# Macro_Keyboard_32u4_Row_Column_MiniMacro.net
KiCad netlist of a schematic drawn in EAGLE
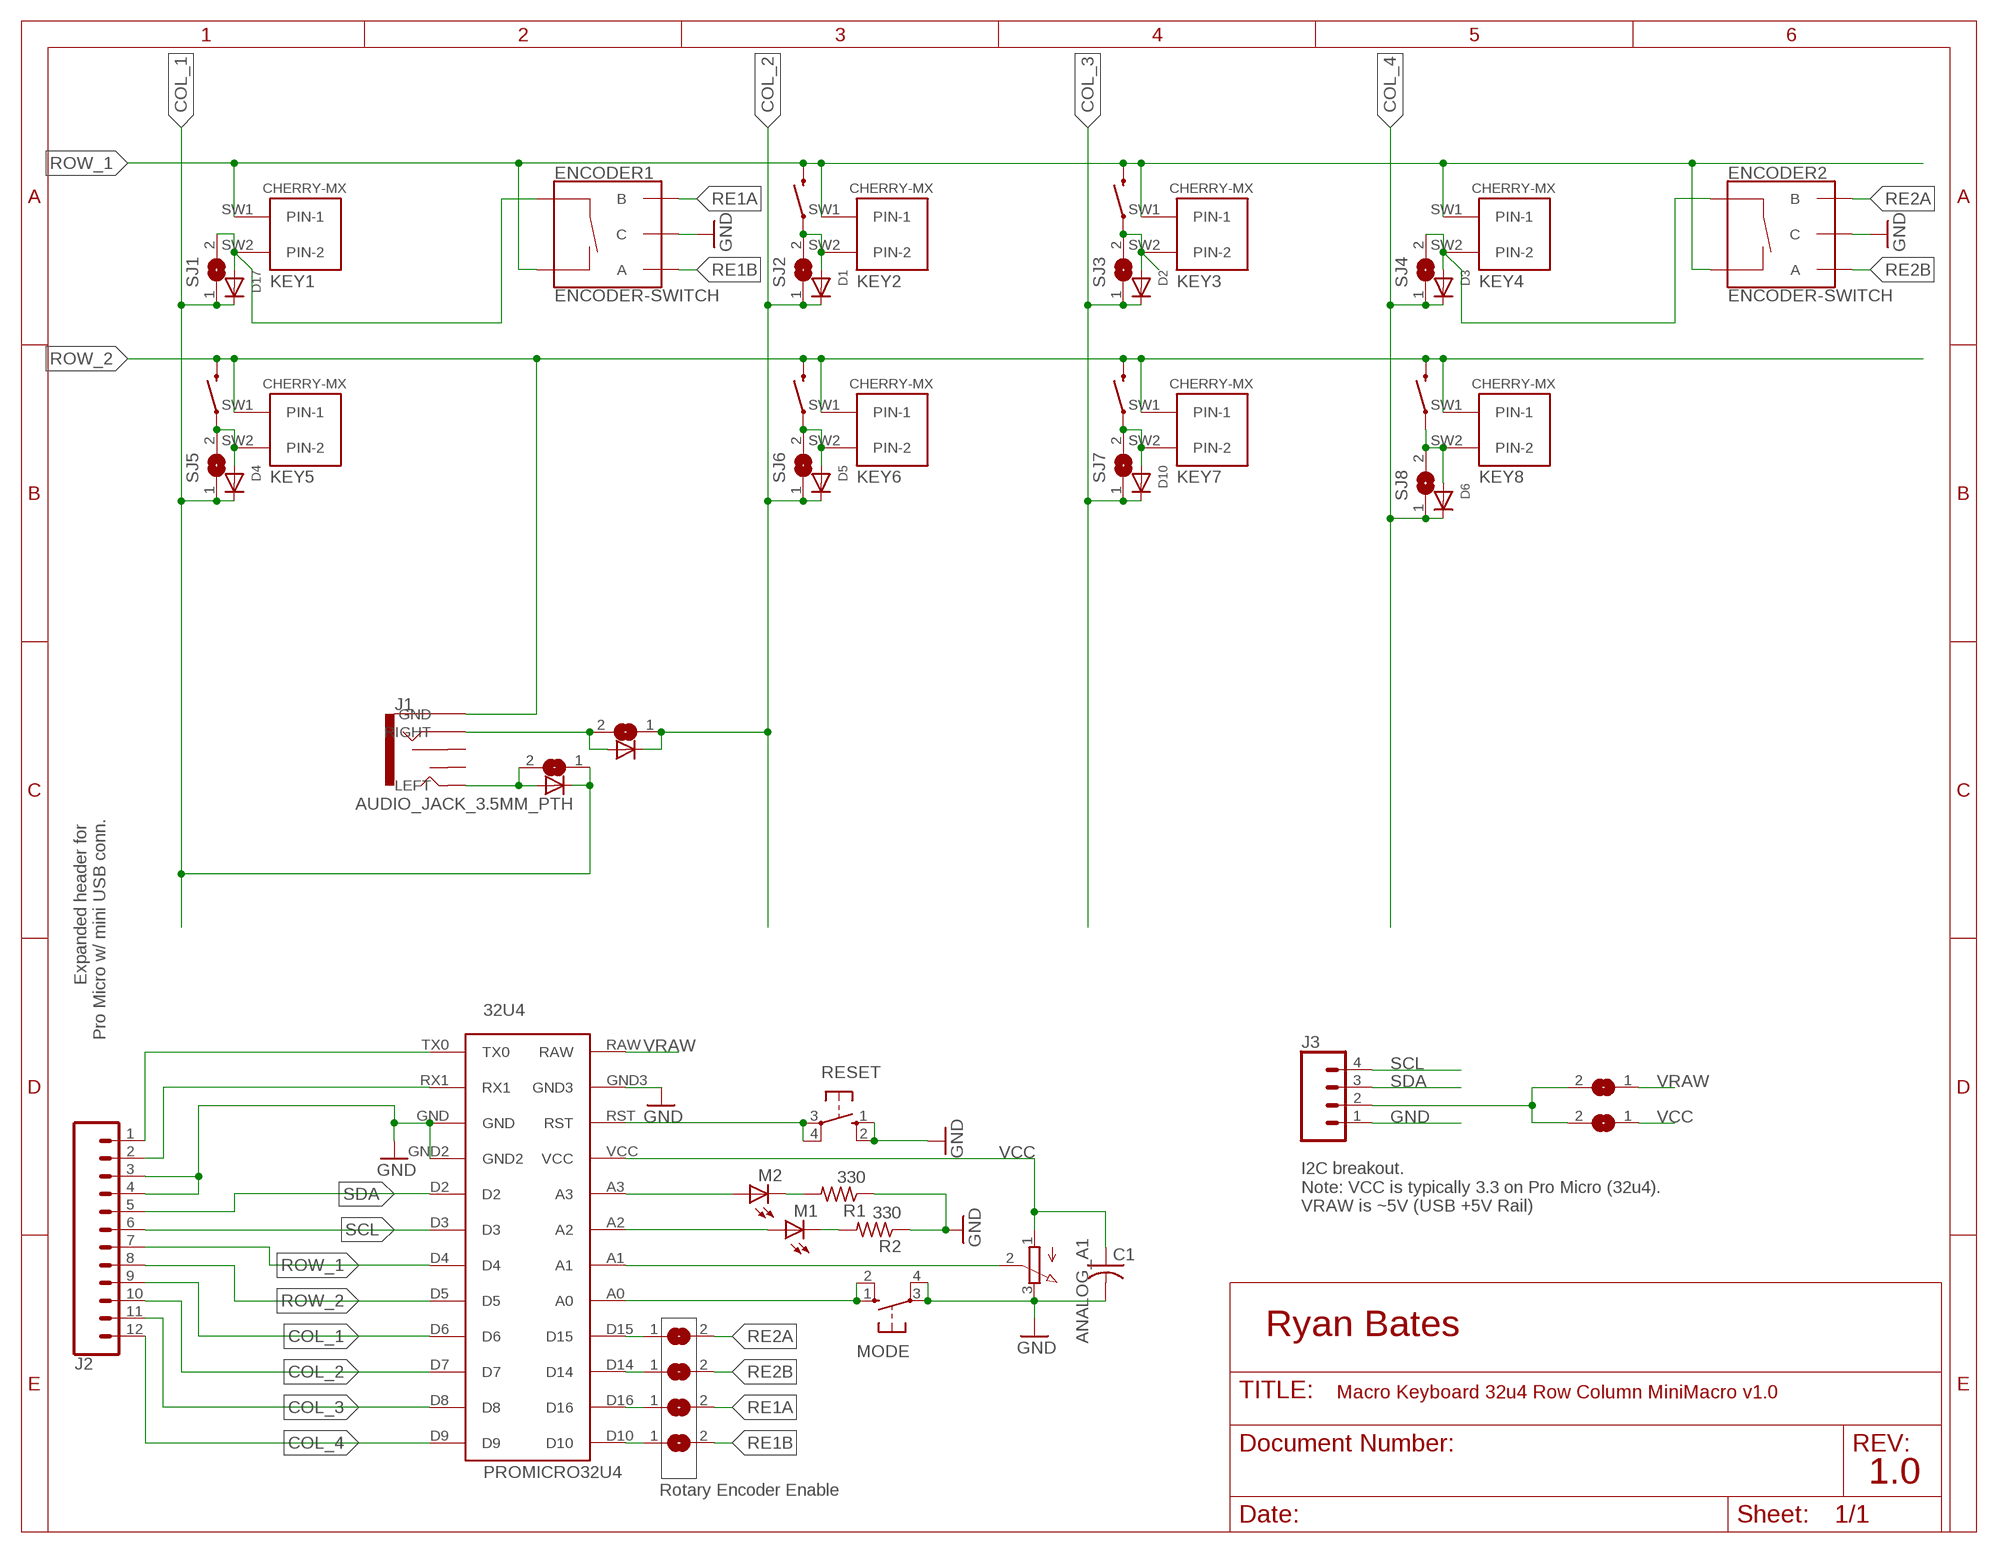
[diagram p0: schematic, sheet 1]

(export (version "E")
  (design (tool "Eeschema 10.0.6"))
  (components
    (comp (ref "32U4")
      (value "PROMICRO32U4")
      (footprint "eagle-import:PROMICRO32U4")
      (libsource (lib "eagle-import") (part "PROMICRO32U4"))
    )
    (comp (ref "ANALOG_A1")
      (value "3RP/1610N")
      (footprint "eagle-import:3RP_1610N")
      (libsource (lib "eagle-import") (part "3RP/1610N"))
    )
    (comp (ref "C1")
      (value "C-USC1206")
      (footprint "eagle-import:C1206")
      (libsource (lib "eagle-import") (part "C-USC1206"))
    )
    (comp (ref "D1")
      (value "DIODESOD-123")
      (footprint "eagle-import:SOD-123")
      (libsource (lib "eagle-import") (part "DIODESOD-123"))
    )
    (comp (ref "D2")
      (value "DIODESOD-123")
      (footprint "eagle-import:SOD-123")
      (libsource (lib "eagle-import") (part "DIODESOD-123"))
    )
    (comp (ref "D3")
      (value "DIODESOD-123")
      (footprint "eagle-import:SOD-123")
      (libsource (lib "eagle-import") (part "DIODESOD-123"))
    )
    (comp (ref "D4")
      (value "DIODESOD-123")
      (footprint "eagle-import:SOD-123")
      (libsource (lib "eagle-import") (part "DIODESOD-123"))
    )
    (comp (ref "D5")
      (value "DIODESOD-123")
      (footprint "eagle-import:SOD-123")
      (libsource (lib "eagle-import") (part "DIODESOD-123"))
    )
    (comp (ref "D6")
      (value "DIODESOD-123")
      (footprint "eagle-import:SOD-123")
      (libsource (lib "eagle-import") (part "DIODESOD-123"))
    )
    (comp (ref "D10")
      (value "DIODESOD-123")
      (footprint "eagle-import:SOD-123")
      (libsource (lib "eagle-import") (part "DIODESOD-123"))
    )
    (comp (ref "D15")
      (value "DIODESOD-123")
      (footprint "eagle-import:SOD-123")
      (libsource (lib "eagle-import") (part "DIODESOD-123"))
    )
    (comp (ref "D16")
      (value "DIODESOD-123")
      (footprint "eagle-import:SOD-123")
      (libsource (lib "eagle-import") (part "DIODESOD-123"))
    )
    (comp (ref "D17")
      (value "DIODESOD-123")
      (footprint "eagle-import:SOD-123")
      (libsource (lib "eagle-import") (part "DIODESOD-123"))
    )
    (comp (ref "ENCODER1")
      (value "ENCODER-SWITCH")
      (footprint "eagle-import:ROTARY_ENC_PLAIN")
      (libsource (lib "eagle-import") (part "ENCODER-SWITCH"))
    )
    (comp (ref "ENCODER2")
      (value "ENCODER-SWITCH")
      (footprint "eagle-import:ROTARY_ENC_PLAIN")
      (libsource (lib "eagle-import") (part "ENCODER-SWITCH"))
    )
    (comp (ref "J1")
      (value "AUDIO_JACK_3.5MM_PTH")
      (footprint "eagle-import:AUDIO-JACK")
      (libsource (lib "eagle-import") (part "AUDIO_JACK_3.5MM_PTH"))
    )
    (comp (ref "J2")
      (value "CONN_12NO_SILK")
      (footprint "eagle-import:1X12_NO_SILK")
      (libsource (lib "eagle-import") (part "CONN_12NO_SILK"))
    )
    (comp (ref "J3")
      (value "CONN_041X04_NO_SILK")
      (footprint "eagle-import:1X04_NO_SILK")
      (libsource (lib "eagle-import") (part "CONN_041X04_NO_SILK"))
    )
    (comp (ref "KEY1")
      (value "CHERRY-MX")
      (footprint "eagle-import:CHERRY-MX")
      (libsource (lib "eagle-import") (part "CHERRY-MX"))
    )
    (comp (ref "KEY2")
      (value "CHERRY-MX")
      (footprint "eagle-import:CHERRY-MX")
      (libsource (lib "eagle-import") (part "CHERRY-MX"))
    )
    (comp (ref "KEY3")
      (value "CHERRY-MX")
      (footprint "eagle-import:CHERRY-MX")
      (libsource (lib "eagle-import") (part "CHERRY-MX"))
    )
    (comp (ref "KEY4")
      (value "CHERRY-MX")
      (footprint "eagle-import:CHERRY-MX")
      (libsource (lib "eagle-import") (part "CHERRY-MX"))
    )
    (comp (ref "KEY5")
      (value "CHERRY-MX")
      (footprint "eagle-import:CHERRY-MX")
      (libsource (lib "eagle-import") (part "CHERRY-MX"))
    )
    (comp (ref "KEY6")
      (value "CHERRY-MX")
      (footprint "eagle-import:CHERRY-MX")
      (libsource (lib "eagle-import") (part "CHERRY-MX"))
    )
    (comp (ref "KEY7")
      (value "CHERRY-MX")
      (footprint "eagle-import:CHERRY-MX")
      (libsource (lib "eagle-import") (part "CHERRY-MX"))
    )
    (comp (ref "KEY8")
      (value "CHERRY-MX")
      (footprint "eagle-import:CHERRY-MX")
      (libsource (lib "eagle-import") (part "CHERRY-MX"))
    )
    (comp (ref "M1")
      (value "LEDCHIPLED_1206")
      (footprint "eagle-import:CHIPLED_1206")
      (libsource (lib "eagle-import") (part "LEDCHIPLED_1206"))
    )
    (comp (ref "M2")
      (value "LEDCHIPLED_1206")
      (footprint "eagle-import:CHIPLED_1206")
      (libsource (lib "eagle-import") (part "LEDCHIPLED_1206"))
    )
    (comp (ref "MODE")
      (value "10-XX")
      (footprint "eagle-import:B3F-10XX")
      (fields (field (name "MPN") "B3F-1000"))
      (libsource (lib "eagle-import") (part "10-XX"))
    )
    (comp (ref "R1")
      (value "330")
      (footprint "eagle-import:R1206")
      (libsource (lib "eagle-import") (part "R-US_R1206"))
    )
    (comp (ref "R2")
      (value "330")
      (footprint "eagle-import:R1206")
      (libsource (lib "eagle-import") (part "R-US_R1206"))
    )
    (comp (ref "RESET")
      (value "10-XX")
      (footprint "eagle-import:B3F-10XX")
      (fields (field (name "MPN") "B3F-1000"))
      (libsource (lib "eagle-import") (part "10-XX"))
    )
    (comp (ref "S1")
      (value "MOMENTARY-SWITCH-SPST-PTH-12MM")
      (footprint "eagle-import:TACTILE_SWITCH_PTH_12MM")
      (libsource (lib "eagle-import") (part "MOMENTARY-SWITCH-SPST-PTH-12MM"))
    )
    (comp (ref "S2")
      (value "MOMENTARY-SWITCH-SPST-PTH-12MM")
      (footprint "eagle-import:TACTILE_SWITCH_PTH_12MM")
      (libsource (lib "eagle-import") (part "MOMENTARY-SWITCH-SPST-PTH-12MM"))
    )
    (comp (ref "S3")
      (value "MOMENTARY-SWITCH-SPST-PTH-12MM")
      (footprint "eagle-import:TACTILE_SWITCH_PTH_12MM")
      (libsource (lib "eagle-import") (part "MOMENTARY-SWITCH-SPST-PTH-12MM"))
    )
    (comp (ref "S4")
      (value "MOMENTARY-SWITCH-SPST-PTH-12MM")
      (footprint "eagle-import:TACTILE_SWITCH_PTH_12MM")
      (libsource (lib "eagle-import") (part "MOMENTARY-SWITCH-SPST-PTH-12MM"))
    )
    (comp (ref "S9")
      (value "MOMENTARY-SWITCH-SPST-PTH-12MM")
      (footprint "eagle-import:TACTILE_SWITCH_PTH_12MM")
      (libsource (lib "eagle-import") (part "MOMENTARY-SWITCH-SPST-PTH-12MM"))
    )
    (comp (ref "S10")
      (value "MOMENTARY-SWITCH-SPST-PTH-12MM")
      (footprint "eagle-import:TACTILE_SWITCH_PTH_12MM")
      (libsource (lib "eagle-import") (part "MOMENTARY-SWITCH-SPST-PTH-12MM"))
    )
    (comp (ref "SJ1") (value "SJ") (footprint "eagle-import:SJ") (libsource (lib "eagle-import") (part "SJ")))
    (comp (ref "SJ2") (value "SJ") (footprint "eagle-import:SJ") (libsource (lib "eagle-import") (part "SJ")))
    (comp (ref "SJ3") (value "SJ") (footprint "eagle-import:SJ") (libsource (lib "eagle-import") (part "SJ")))
    (comp (ref "SJ4") (value "SJ") (footprint "eagle-import:SJ") (libsource (lib "eagle-import") (part "SJ")))
    (comp (ref "SJ5") (value "SJ") (footprint "eagle-import:SJ") (libsource (lib "eagle-import") (part "SJ")))
    (comp (ref "SJ6") (value "SJ") (footprint "eagle-import:SJ") (libsource (lib "eagle-import") (part "SJ")))
    (comp (ref "SJ7") (value "SJ") (footprint "eagle-import:SJ") (libsource (lib "eagle-import") (part "SJ")))
    (comp (ref "SJ8") (value "SJ") (footprint "eagle-import:SJ") (libsource (lib "eagle-import") (part "SJ")))
    (comp (ref "SJ9") (value "SJ") (footprint "eagle-import:SJ") (libsource (lib "eagle-import") (part "SJ")))
    (comp (ref "SJ10")
      (value "SJ")
      (footprint "eagle-import:SJ")
      (libsource (lib "eagle-import") (part "SJ"))
    )
    (comp (ref "SJ16")
      (value "SJ")
      (footprint "eagle-import:SJ")
      (libsource (lib "eagle-import") (part "SJ"))
    )
    (comp (ref "SJ17")
      (value "SJ")
      (footprint "eagle-import:SJ")
      (libsource (lib "eagle-import") (part "SJ"))
    )
    (comp (ref "SJ18")
      (value "SJ")
      (footprint "eagle-import:SJ")
      (libsource (lib "eagle-import") (part "SJ"))
    )
    (comp (ref "SJ19")
      (value "SJ")
      (footprint "eagle-import:SJ")
      (libsource (lib "eagle-import") (part "SJ"))
    )
    (comp (ref "SJ20")
      (value "SJ")
      (footprint "eagle-import:SJ")
      (libsource (lib "eagle-import") (part "SJ"))
    )
    (comp (ref "SJ21")
      (value "SJ")
      (footprint "eagle-import:SJ")
      (libsource (lib "eagle-import") (part "SJ"))
    )
  )
  (nets
    (net (code "1") (name "/VCC") (class "Default")
      (node (ref "32U4") (pin "VCC") (pinfunction "VCC_VCC") (pintype "bidirectional"))
      (node (ref "ANALOG_A1") (pin "1") (pinfunction "A_1") (pintype "passive"))
      (node (ref "C1") (pin "1") (pinfunction "1_1") (pintype "passive"))
      (node (ref "SJ10") (pin "1") (pinfunction "1_1") (pintype "passive"))
    )
    (net (code "2") (name "/VRAW") (class "Default")
      (node (ref "32U4") (pin "RAW") (pinfunction "RAW_RAW") (pintype "bidirectional"))
      (node (ref "SJ9") (pin "1") (pinfunction "1_1") (pintype "passive"))
    )
    (net (code "3") (name "COL_1") (class "Default")
      (node (ref "32U4") (pin "D6") (pinfunction "D6_D6") (pintype "bidirectional"))
      (node (ref "D15") (pin "C") (pinfunction "C_C") (pintype "passive"))
      (node (ref "D17") (pin "C") (pinfunction "C_C") (pintype "passive"))
      (node (ref "D4") (pin "C") (pinfunction "C_C") (pintype "passive"))
      (node (ref "J2") (pin "9") (pinfunction "9_9") (pintype "passive"))
      (node (ref "SJ1") (pin "1") (pinfunction "1_1") (pintype "passive"))
      (node (ref "SJ16") (pin "1") (pinfunction "1_1") (pintype "passive"))
      (node (ref "SJ5") (pin "1") (pinfunction "1_1") (pintype "passive"))
    )
    (net (code "4") (name "COL_2") (class "Default")
      (node (ref "32U4") (pin "D7") (pinfunction "D7_D7") (pintype "bidirectional"))
      (node (ref "D1") (pin "C") (pinfunction "C_C") (pintype "passive"))
      (node (ref "D16") (pin "C") (pinfunction "C_C") (pintype "passive"))
      (node (ref "D5") (pin "C") (pinfunction "C_C") (pintype "passive"))
      (node (ref "J2") (pin "10") (pinfunction "10_10") (pintype "passive"))
      (node (ref "SJ17") (pin "1") (pinfunction "1_1") (pintype "passive"))
      (node (ref "SJ2") (pin "1") (pinfunction "1_1") (pintype "passive"))
      (node (ref "SJ6") (pin "1") (pinfunction "1_1") (pintype "passive"))
    )
    (net (code "5") (name "COL_3") (class "Default")
      (node (ref "32U4") (pin "D8") (pinfunction "D8_D8") (pintype "bidirectional"))
      (node (ref "D10") (pin "C") (pinfunction "C_C") (pintype "passive"))
      (node (ref "D2") (pin "C") (pinfunction "C_C") (pintype "passive"))
      (node (ref "J2") (pin "11") (pinfunction "11_11") (pintype "passive"))
      (node (ref "SJ3") (pin "1") (pinfunction "1_1") (pintype "passive"))
      (node (ref "SJ7") (pin "1") (pinfunction "1_1") (pintype "passive"))
    )
    (net (code "6") (name "COL_4") (class "Default")
      (node (ref "32U4") (pin "D9") (pinfunction "D9_D9") (pintype "bidirectional"))
      (node (ref "D3") (pin "C") (pinfunction "C_C") (pintype "passive"))
      (node (ref "D6") (pin "C") (pinfunction "C_C") (pintype "passive"))
      (node (ref "J2") (pin "12") (pinfunction "12_12") (pintype "passive"))
      (node (ref "SJ4") (pin "1") (pinfunction "1_1") (pintype "passive"))
      (node (ref "SJ8") (pin "1") (pinfunction "1_1") (pintype "passive"))
    )
    (net (code "7") (name "GND") (class "Default")
      (node (ref "32U4") (pin "GND") (pinfunction "GND_GND") (pintype "bidirectional"))
      (node (ref "32U4") (pin "GND2") (pinfunction "GND2_GND2") (pintype "bidirectional"))
      (node (ref "32U4") (pin "GND3") (pinfunction "GND3_GND3") (pintype "bidirectional"))
      (node (ref "ANALOG_A1") (pin "3") (pinfunction "E_3") (pintype "passive"))
      (node (ref "C1") (pin "2") (pinfunction "2_2") (pintype "passive"))
      (node (ref "ENCODER1") (pin "C") (pinfunction "C_C") (pintype "bidirectional"))
      (node (ref "ENCODER2") (pin "C") (pinfunction "C_C") (pintype "bidirectional"))
      (node (ref "J2") (pin "3") (pinfunction "3_3") (pintype "passive"))
      (node (ref "J2") (pin "4") (pinfunction "4_4") (pintype "passive"))
      (node (ref "J3") (pin "1") (pinfunction "1_1") (pintype "passive"))
      (node (ref "MODE") (pin "3") (pinfunction "P_3") (pintype "passive"))
      (node (ref "MODE") (pin "4") (pinfunction "P1_4") (pintype "passive"))
      (node (ref "R1") (pin "1") (pinfunction "1_1") (pintype "passive"))
      (node (ref "R2") (pin "1") (pinfunction "1_1") (pintype "passive"))
      (node (ref "RESET") (pin "1") (pinfunction "S_1") (pintype "passive"))
      (node (ref "RESET") (pin "2") (pinfunction "S1_2") (pintype "passive"))
    )
    (net (code "8") (name "Net-(32U4-PadA2)") (class "Default")
      (node (ref "32U4") (pin "A2") (pinfunction "A2_A2") (pintype "bidirectional"))
      (node (ref "M1") (pin "A") (pinfunction "A_A") (pintype "passive"))
    )
    (net (code "9") (name "Net-(32U4-PadA3)") (class "Default")
      (node (ref "32U4") (pin "A3") (pinfunction "A3_A3") (pintype "bidirectional"))
      (node (ref "M2") (pin "A") (pinfunction "A_A") (pintype "passive"))
    )
    (net (code "10") (name "Net-(32U4-PadD10)") (class "Default")
      (node (ref "32U4") (pin "D10") (pinfunction "D10_D10") (pintype "bidirectional"))
      (node (ref "SJ21") (pin "1") (pinfunction "1_1") (pintype "passive"))
    )
    (net (code "11") (name "Net-(32U4-PadD14)") (class "Default")
      (node (ref "32U4") (pin "D14") (pinfunction "D14_D14") (pintype "bidirectional"))
      (node (ref "SJ19") (pin "1") (pinfunction "1_1") (pintype "passive"))
    )
    (net (code "12") (name "Net-(32U4-PadD15)") (class "Default")
      (node (ref "32U4") (pin "D15") (pinfunction "D15_D15") (pintype "bidirectional"))
      (node (ref "SJ18") (pin "1") (pinfunction "1_1") (pintype "passive"))
    )
    (net (code "13") (name "Net-(32U4-PadD16)") (class "Default")
      (node (ref "32U4") (pin "D16") (pinfunction "D16_D16") (pintype "bidirectional"))
      (node (ref "SJ20") (pin "1") (pinfunction "1_1") (pintype "passive"))
    )
    (net (code "14") (name "Net-(32U4-PadRX1)") (class "Default")
      (node (ref "32U4") (pin "RX1") (pinfunction "RX1_RX1") (pintype "bidirectional"))
      (node (ref "J2") (pin "2") (pinfunction "2_2") (pintype "passive"))
    )
    (net (code "15") (name "Net-(32U4-PadTX0)") (class "Default")
      (node (ref "32U4") (pin "TX0") (pinfunction "TX0_TX0") (pintype "bidirectional"))
      (node (ref "J2") (pin "1") (pinfunction "1_1") (pintype "passive"))
    )
    (net (code "16") (name "Net-(ANALOG_A1-S)") (class "Default")
      (node (ref "32U4") (pin "A1") (pinfunction "A1_A1") (pintype "bidirectional"))
      (node (ref "ANALOG_A1") (pin "2") (pinfunction "S_2") (pintype "passive"))
    )
    (net (code "17") (name "Net-(D15-PadA)") (class "Default")
      (node (ref "D15") (pin "A") (pinfunction "A_A") (pintype "passive"))
      (node (ref "J1") (pin "LEFT") (pinfunction "LEFT_LEFT") (pintype "bidirectional"))
      (node (ref "SJ16") (pin "2") (pinfunction "2_2") (pintype "passive"))
    )
    (net (code "18") (name "Net-(D16-PadA)") (class "Default")
      (node (ref "D16") (pin "A") (pinfunction "A_A") (pintype "passive"))
      (node (ref "J1") (pin "RIGHT") (pinfunction "RIGHT_RIGHT") (pintype "bidirectional"))
      (node (ref "SJ17") (pin "2") (pinfunction "2_2") (pintype "passive"))
    )
    (net (code "19") (name "Net-(J3-Pad2)") (class "Default")
      (node (ref "J3") (pin "2") (pinfunction "2_2") (pintype "passive"))
      (node (ref "SJ10") (pin "2") (pinfunction "2_2") (pintype "passive"))
      (node (ref "SJ9") (pin "2") (pinfunction "2_2") (pintype "passive"))
    )
    (net (code "20") (name "Net-(KEY1-PIN-2)") (class "Default")
      (node (ref "D17") (pin "A") (pinfunction "A_A") (pintype "passive"))
      (node (ref "ENCODER1") (pin "SW+") (pinfunction "SW+_SW+") (pintype "bidirectional"))
      (node (ref "KEY1") (pin "SW2") (pinfunction "PIN-2_SW2") (pintype "bidirectional"))
      (node (ref "SJ1") (pin "2") (pinfunction "2_2") (pintype "passive"))
    )
    (net (code "21") (name "Net-(KEY2-PIN-2)") (class "Default")
      (node (ref "D1") (pin "A") (pinfunction "A_A") (pintype "passive"))
      (node (ref "KEY2") (pin "SW2") (pinfunction "PIN-2_SW2") (pintype "bidirectional"))
      (node (ref "S4") (pin "1") (pinfunction "1_1") (pintype "passive"))
      (node (ref "SJ2") (pin "2") (pinfunction "2_2") (pintype "passive"))
    )
    (net (code "22") (name "Net-(KEY3-PIN-2)") (class "Default")
      (node (ref "D2") (pin "A") (pinfunction "A_A") (pintype "passive"))
      (node (ref "KEY3") (pin "SW2") (pinfunction "PIN-2_SW2") (pintype "bidirectional"))
      (node (ref "S3") (pin "1") (pinfunction "1_1") (pintype "passive"))
      (node (ref "SJ3") (pin "2") (pinfunction "2_2") (pintype "passive"))
    )
    (net (code "23") (name "Net-(KEY4-PIN-2)") (class "Default")
      (node (ref "D3") (pin "A") (pinfunction "A_A") (pintype "passive"))
      (node (ref "ENCODER2") (pin "SW+") (pinfunction "SW+_SW+") (pintype "bidirectional"))
      (node (ref "KEY4") (pin "SW2") (pinfunction "PIN-2_SW2") (pintype "bidirectional"))
      (node (ref "SJ4") (pin "2") (pinfunction "2_2") (pintype "passive"))
    )
    (net (code "24") (name "Net-(KEY5-PIN-2)") (class "Default")
      (node (ref "D4") (pin "A") (pinfunction "A_A") (pintype "passive"))
      (node (ref "KEY5") (pin "SW2") (pinfunction "PIN-2_SW2") (pintype "bidirectional"))
      (node (ref "S9") (pin "1") (pinfunction "1_1") (pintype "passive"))
      (node (ref "SJ5") (pin "2") (pinfunction "2_2") (pintype "passive"))
    )
    (net (code "25") (name "Net-(KEY6-PIN-2)") (class "Default")
      (node (ref "D5") (pin "A") (pinfunction "A_A") (pintype "passive"))
      (node (ref "KEY6") (pin "SW2") (pinfunction "PIN-2_SW2") (pintype "bidirectional"))
      (node (ref "S10") (pin "1") (pinfunction "1_1") (pintype "passive"))
      (node (ref "SJ6") (pin "2") (pinfunction "2_2") (pintype "passive"))
    )
    (net (code "26") (name "Net-(KEY7-PIN-2)") (class "Default")
      (node (ref "D10") (pin "A") (pinfunction "A_A") (pintype "passive"))
      (node (ref "KEY7") (pin "SW2") (pinfunction "PIN-2_SW2") (pintype "bidirectional"))
      (node (ref "S1") (pin "1") (pinfunction "1_1") (pintype "passive"))
      (node (ref "SJ7") (pin "2") (pinfunction "2_2") (pintype "passive"))
    )
    (net (code "27") (name "Net-(KEY8-PIN-2)") (class "Default")
      (node (ref "D6") (pin "A") (pinfunction "A_A") (pintype "passive"))
      (node (ref "KEY8") (pin "SW2") (pinfunction "PIN-2_SW2") (pintype "bidirectional"))
      (node (ref "S2") (pin "1") (pinfunction "1_1") (pintype "passive"))
      (node (ref "SJ8") (pin "2") (pinfunction "2_2") (pintype "passive"))
    )
    (net (code "28") (name "Net-(M1-PadC)") (class "Default")
      (node (ref "M1") (pin "C") (pinfunction "C_C") (pintype "passive"))
      (node (ref "R2") (pin "2") (pinfunction "2_2") (pintype "passive"))
    )
    (net (code "29") (name "Net-(M2-PadC)") (class "Default")
      (node (ref "M2") (pin "C") (pinfunction "C_C") (pintype "passive"))
      (node (ref "R1") (pin "2") (pinfunction "2_2") (pintype "passive"))
    )
    (net (code "30") (name "Net-(MODE-S)") (class "Default")
      (node (ref "32U4") (pin "A0") (pinfunction "A0_A0") (pintype "bidirectional"))
      (node (ref "MODE") (pin "1") (pinfunction "S_1") (pintype "passive"))
      (node (ref "MODE") (pin "2") (pinfunction "S1_2") (pintype "passive"))
    )
    (net (code "31") (name "Net-(RESET-P)") (class "Default")
      (node (ref "32U4") (pin "RST") (pinfunction "RST_RST") (pintype "bidirectional"))
      (node (ref "RESET") (pin "3") (pinfunction "P_3") (pintype "passive"))
      (node (ref "RESET") (pin "4") (pinfunction "P1_4") (pintype "passive"))
    )
    (net (code "32") (name "RE1A") (class "Default")
      (node (ref "ENCODER1") (pin "B") (pinfunction "B_B") (pintype "bidirectional"))
      (node (ref "SJ20") (pin "2") (pinfunction "2_2") (pintype "passive"))
    )
    (net (code "33") (name "RE1B") (class "Default")
      (node (ref "ENCODER1") (pin "A") (pinfunction "A_A") (pintype "bidirectional"))
      (node (ref "SJ21") (pin "2") (pinfunction "2_2") (pintype "passive"))
    )
    (net (code "34") (name "RE2A") (class "Default")
      (node (ref "ENCODER2") (pin "B") (pinfunction "B_B") (pintype "bidirectional"))
      (node (ref "SJ18") (pin "2") (pinfunction "2_2") (pintype "passive"))
    )
    (net (code "35") (name "RE2B") (class "Default")
      (node (ref "ENCODER2") (pin "A") (pinfunction "A_A") (pintype "bidirectional"))
      (node (ref "SJ19") (pin "2") (pinfunction "2_2") (pintype "passive"))
    )
    (net (code "36") (name "ROW_1") (class "Default")
      (node (ref "32U4") (pin "D4") (pinfunction "D4_D4") (pintype "bidirectional"))
      (node (ref "ENCODER1") (pin "SW-") (pinfunction "SW-_SW-") (pintype "bidirectional"))
      (node (ref "ENCODER2") (pin "SW-") (pinfunction "SW-_SW-") (pintype "bidirectional"))
      (node (ref "J2") (pin "7") (pinfunction "7_7") (pintype "passive"))
      (node (ref "KEY1") (pin "SW1") (pinfunction "PIN-1_SW1") (pintype "bidirectional"))
      (node (ref "KEY2") (pin "SW1") (pinfunction "PIN-1_SW1") (pintype "bidirectional"))
      (node (ref "KEY3") (pin "SW1") (pinfunction "PIN-1_SW1") (pintype "bidirectional"))
      (node (ref "KEY4") (pin "SW1") (pinfunction "PIN-1_SW1") (pintype "bidirectional"))
      (node (ref "S3") (pin "3") (pinfunction "2_3") (pintype "passive"))
      (node (ref "S4") (pin "3") (pinfunction "2_3") (pintype "passive"))
    )
    (net (code "37") (name "ROW_2") (class "Default")
      (node (ref "32U4") (pin "D5") (pinfunction "D5_D5") (pintype "bidirectional"))
      (node (ref "J1") (pin "GND") (pinfunction "GND_GND") (pintype "bidirectional"))
      (node (ref "J2") (pin "8") (pinfunction "8_8") (pintype "passive"))
      (node (ref "KEY5") (pin "SW1") (pinfunction "PIN-1_SW1") (pintype "bidirectional"))
      (node (ref "KEY6") (pin "SW1") (pinfunction "PIN-1_SW1") (pintype "bidirectional"))
      (node (ref "KEY7") (pin "SW1") (pinfunction "PIN-1_SW1") (pintype "bidirectional"))
      (node (ref "KEY8") (pin "SW1") (pinfunction "PIN-1_SW1") (pintype "bidirectional"))
      (node (ref "S1") (pin "3") (pinfunction "2_3") (pintype "passive"))
      (node (ref "S10") (pin "3") (pinfunction "2_3") (pintype "passive"))
      (node (ref "S2") (pin "3") (pinfunction "2_3") (pintype "passive"))
      (node (ref "S9") (pin "3") (pinfunction "2_3") (pintype "passive"))
    )
    (net (code "38") (name "SCL") (class "Default")
      (node (ref "32U4") (pin "D3") (pinfunction "D3_D3") (pintype "bidirectional"))
      (node (ref "J2") (pin "6") (pinfunction "6_6") (pintype "passive"))
      (node (ref "J3") (pin "4") (pinfunction "4_4") (pintype "passive"))
    )
    (net (code "39") (name "SDA") (class "Default")
      (node (ref "32U4") (pin "D2") (pinfunction "D2_D2") (pintype "bidirectional"))
      (node (ref "J2") (pin "5") (pinfunction "5_5") (pintype "passive"))
      (node (ref "J3") (pin "3") (pinfunction "3_3") (pintype "passive"))
    )
    (net (code "40") (name "unconnected-(J1-PadRSH)") (class "Default")
      (node (ref "J1") (pin "RSH") (pinfunction "RSH_RSH") (pintype "bidirectional"))
    )
    (net (code "41") (name "unconnected-(J1-PadTSH)") (class "Default")
      (node (ref "J1") (pin "TSH") (pinfunction "TSH_TSH") (pintype "bidirectional"))
    )
  )
)
